# Microcontroller.net
KiCad netlist of a schematic drawn in Altium Designer
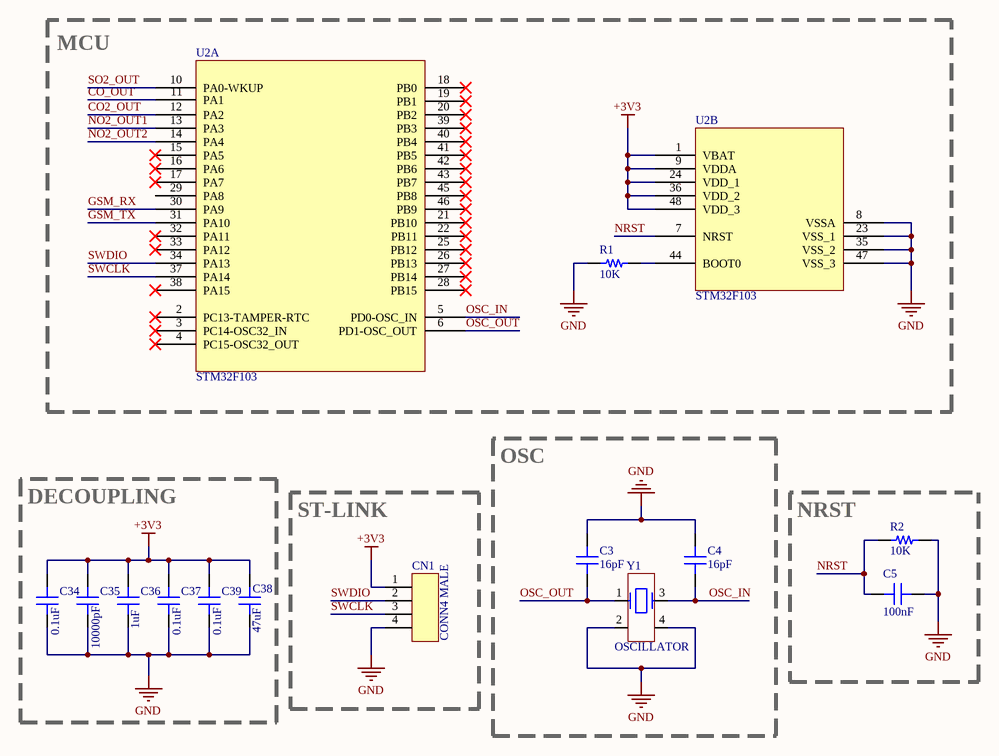
[diagram p0: Microcontroller.SchDoc]

(export (version "E")
  (design (tool "Eeschema 10.0.6"))
  (components
    (comp (ref "C3")
      (value "16pF")
      (footprint "CAP 0603_1608")
      (description "CERAMİC 1206 SMD")
      (libsource (lib "hava_kalitesi_olcumu") (part "16pF"))
    )
    (comp (ref "C4")
      (value "16pF")
      (footprint "CAP 0603_1608")
      (description "CERAMİC 1206 SMD")
      (libsource (lib "hava_kalitesi_olcumu") (part "16pF"))
    )
    (comp (ref "C5")
      (value "100nF")
      (footprint "CAP 0603_1608")
      (description "CERAMİC 1206 SMD")
      (libsource (lib "hava_kalitesi_olcumu") (part "100nF"))
    )
    (comp (ref "C34")
      (value "0.1uF")
      (footprint "CAP 0603_1608")
      (description "CERAMİC 1206 SMD")
      (libsource (lib "hava_kalitesi_olcumu") (part "0.1uF"))
    )
    (comp (ref "C35")
      (value "10000pF")
      (footprint "CAP 0603_1608")
      (description "CERAMİC 1206 SMD")
      (libsource (lib "hava_kalitesi_olcumu") (part "10000pF"))
    )
    (comp (ref "C36")
      (value "1uF")
      (footprint "CAP 0603_1608")
      (description "CERAMİC 1206 SMD")
      (libsource (lib "hava_kalitesi_olcumu") (part "1uF"))
    )
    (comp (ref "C37")
      (value "0.1uF")
      (footprint "CAP 0603_1608")
      (description "CERAMİC 1206 SMD")
      (libsource (lib "hava_kalitesi_olcumu") (part "0.1uF"))
    )
    (comp (ref "C38")
      (value "47uF")
      (footprint "CAP 0603_1608")
      (description "CERAMİC 1206 SMD")
      (libsource (lib "hava_kalitesi_olcumu") (part "47uF"))
    )
    (comp (ref "C39")
      (value "0.1uF")
      (footprint "CAP 0603_1608")
      (description "CERAMİC 1206 SMD")
      (libsource (lib "hava_kalitesi_olcumu") (part "0.1uF"))
    )
    (comp (ref "CN1")
      (value "CONN4 MALE")
      (footprint "CONN4 MALE")
      (description "4 PIN 2.54MM")
      (libsource (lib "hava_kalitesi_olcumu") (part "CONN4 MALE"))
    )
    (comp (ref "R1")
      (value "10K")
      (footprint "RES 0603_1608")
      (description "SMT RES 1206")
      (libsource (lib "hava_kalitesi_olcumu") (part "10K"))
    )
    (comp (ref "R2")
      (value "10K")
      (footprint "RES 0603_1608")
      (description "SMT RES 1206")
      (libsource (lib "hava_kalitesi_olcumu") (part "10K"))
    )
    (comp (ref "U2")
      (value "STM32F103")
      (footprint "LQFP48")
      (description "STM32F103C8T6 SMD LQFP-48 32-Bit 72 MHz Mikrodenetleyici")
      (libsource (lib "hava_kalitesi_olcumu") (part "STM32F103"))
    )
    (comp (ref "Y1")
      (value "OSCILLATOR")
      (footprint "OSCILLATOR")
      (description "8MHZ 12.5pF")
      (libsource (lib "hava_kalitesi_olcumu") (part "OSCILLATOR"))
    )
  )
  (nets
    (net (code "1") (name "+3V3") (class "Default")
      (node (ref "C34") (pin "2") (pinfunction "2_2") (pintype "passive"))
      (node (ref "C35") (pin "2") (pinfunction "2_2") (pintype "passive"))
      (node (ref "C36") (pin "2") (pinfunction "2_2") (pintype "passive"))
      (node (ref "C37") (pin "2") (pinfunction "2_2") (pintype "passive"))
      (node (ref "C38") (pin "2") (pinfunction "2_2") (pintype "passive"))
      (node (ref "C39") (pin "2") (pinfunction "2_2") (pintype "passive"))
      (node (ref "CN1") (pin "1") (pintype "passive"))
      (node (ref "U2") (pin "1") (pinfunction "VBAT_1") (pintype "passive"))
      (node (ref "U2") (pin "24") (pinfunction "VDD_1_24") (pintype "passive"))
      (node (ref "U2") (pin "36") (pinfunction "VDD_2_36") (pintype "passive"))
      (node (ref "U2") (pin "48") (pinfunction "VDD_3_48") (pintype "passive"))
      (node (ref "U2") (pin "9") (pinfunction "VDDA_9") (pintype "passive"))
    )
    (net (code "2") (name "/CO2_OUT") (class "Default")
      (node (ref "U2") (pin "12") (pinfunction "PA2_12") (pintype "passive"))
    )
    (net (code "3") (name "/CO_OUT") (class "Default")
      (node (ref "U2") (pin "11") (pinfunction "PA1_11") (pintype "passive"))
    )
    (net (code "4") (name "/GSM_RX") (class "Default")
      (node (ref "U2") (pin "30") (pinfunction "PA9_30") (pintype "passive"))
    )
    (net (code "5") (name "/GSM_TX") (class "Default")
      (node (ref "U2") (pin "31") (pinfunction "PA10_31") (pintype "passive"))
    )
    (net (code "6") (name "/NO2_OUT1") (class "Default")
      (node (ref "U2") (pin "13") (pinfunction "PA3_13") (pintype "passive"))
    )
    (net (code "7") (name "/NO2_OUT2") (class "Default")
      (node (ref "U2") (pin "14") (pinfunction "PA4_14") (pintype "passive"))
    )
    (net (code "8") (name "/NRST") (class "Default")
      (node (ref "C5") (pin "2") (pinfunction "2_2") (pintype "passive"))
      (node (ref "R2") (pin "1") (pinfunction "1_1") (pintype "passive"))
      (node (ref "U2") (pin "7") (pinfunction "NRST_7") (pintype "passive"))
    )
    (net (code "9") (name "/OSC_IN") (class "Default")
      (node (ref "C4") (pin "1") (pinfunction "1_1") (pintype "passive"))
      (node (ref "U2") (pin "5") (pinfunction "PD0-OSC_IN_5") (pintype "passive"))
      (node (ref "Y1") (pin "3") (pinfunction "3_3") (pintype "passive"))
    )
    (net (code "10") (name "/OSC_OUT") (class "Default")
      (node (ref "C3") (pin "1") (pinfunction "1_1") (pintype "passive"))
      (node (ref "U2") (pin "6") (pinfunction "PD1-OSC_OUT_6") (pintype "passive"))
      (node (ref "Y1") (pin "1") (pinfunction "1_1") (pintype "passive"))
    )
    (net (code "11") (name "/SO2_OUT") (class "Default")
      (node (ref "U2") (pin "10") (pinfunction "PA0-WKUP_10") (pintype "passive"))
    )
    (net (code "12") (name "/SWCLK") (class "Default")
      (node (ref "CN1") (pin "3") (pintype "passive"))
      (node (ref "U2") (pin "37") (pinfunction "PA14_37") (pintype "passive"))
    )
    (net (code "13") (name "/SWDIO") (class "Default")
      (node (ref "CN1") (pin "2") (pintype "passive"))
      (node (ref "U2") (pin "34") (pinfunction "PA13_34") (pintype "passive"))
    )
    (net (code "14") (name "GND") (class "Default")
      (node (ref "C3") (pin "2") (pinfunction "2_2") (pintype "passive"))
      (node (ref "C34") (pin "1") (pinfunction "1_1") (pintype "passive"))
      (node (ref "C35") (pin "1") (pinfunction "1_1") (pintype "passive"))
      (node (ref "C36") (pin "1") (pinfunction "1_1") (pintype "passive"))
      (node (ref "C37") (pin "1") (pinfunction "1_1") (pintype "passive"))
      (node (ref "C38") (pin "1") (pinfunction "1_1") (pintype "passive"))
      (node (ref "C39") (pin "1") (pinfunction "1_1") (pintype "passive"))
      (node (ref "C4") (pin "2") (pinfunction "2_2") (pintype "passive"))
      (node (ref "C5") (pin "1") (pinfunction "1_1") (pintype "passive"))
      (node (ref "CN1") (pin "4") (pintype "passive"))
      (node (ref "R1") (pin "1") (pinfunction "1_1") (pintype "passive"))
      (node (ref "R2") (pin "2") (pinfunction "2_2") (pintype "passive"))
      (node (ref "U2") (pin "23") (pinfunction "VSS_1_23") (pintype "passive"))
      (node (ref "U2") (pin "35") (pinfunction "VSS_2_35") (pintype "passive"))
      (node (ref "U2") (pin "47") (pinfunction "VSS_3_47") (pintype "passive"))
      (node (ref "U2") (pin "8") (pinfunction "VSSA_8") (pintype "passive"))
      (node (ref "Y1") (pin "2") (pinfunction "2_2") (pintype "passive"))
      (node (ref "Y1") (pin "4") (pinfunction "4_4") (pintype "passive"))
    )
    (net (code "15") (name "Net-(U2B-BOOT0)") (class "Default")
      (node (ref "R1") (pin "2") (pinfunction "2_2") (pintype "passive"))
      (node (ref "U2") (pin "44") (pinfunction "BOOT0_44") (pintype "passive"))
    )
    (net (code "16") (name "unconnected-(U2A-PA1-Pad11)") (class "Default")
      (node (ref "U2") (pin "11") (pinfunction "PA1_11") (pintype "passive"))
    )
    (net (code "17") (name "unconnected-(U2A-PA5-Pad15)") (class "Default")
      (node (ref "U2") (pin "15") (pinfunction "PA5_15") (pintype "passive+no_connect"))
    )
    (net (code "18") (name "unconnected-(U2A-PA6-Pad16)") (class "Default")
      (node (ref "U2") (pin "16") (pinfunction "PA6_16") (pintype "passive+no_connect"))
    )
    (net (code "19") (name "unconnected-(U2A-PA7-Pad17)") (class "Default")
      (node (ref "U2") (pin "17") (pinfunction "PA7_17") (pintype "passive+no_connect"))
    )
    (net (code "20") (name "unconnected-(U2A-PA8-Pad29)") (class "Default")
      (node (ref "U2") (pin "29") (pinfunction "PA8_29") (pintype "passive"))
    )
    (net (code "21") (name "unconnected-(U2A-PA11-Pad32)") (class "Default")
      (node (ref "U2") (pin "32") (pinfunction "PA11_32") (pintype "passive+no_connect"))
    )
    (net (code "22") (name "unconnected-(U2A-PA12-Pad33)") (class "Default")
      (node (ref "U2") (pin "33") (pinfunction "PA12_33") (pintype "passive+no_connect"))
    )
    (net (code "23") (name "unconnected-(U2A-PA15-Pad38)") (class "Default")
      (node (ref "U2") (pin "38") (pinfunction "PA15_38") (pintype "passive+no_connect"))
    )
    (net (code "24") (name "unconnected-(U2A-PB0-Pad18)") (class "Default")
      (node (ref "U2") (pin "18") (pinfunction "PB0_18") (pintype "passive+no_connect"))
    )
    (net (code "25") (name "unconnected-(U2A-PB1-Pad19)") (class "Default")
      (node (ref "U2") (pin "19") (pinfunction "PB1_19") (pintype "passive+no_connect"))
    )
    (net (code "26") (name "unconnected-(U2A-PB2-Pad20)") (class "Default")
      (node (ref "U2") (pin "20") (pinfunction "PB2_20") (pintype "passive+no_connect"))
    )
    (net (code "27") (name "unconnected-(U2A-PB3-Pad39)") (class "Default")
      (node (ref "U2") (pin "39") (pinfunction "PB3_39") (pintype "passive+no_connect"))
    )
    (net (code "28") (name "unconnected-(U2A-PB4-Pad40)") (class "Default")
      (node (ref "U2") (pin "40") (pinfunction "PB4_40") (pintype "passive+no_connect"))
    )
    (net (code "29") (name "unconnected-(U2A-PB5-Pad41)") (class "Default")
      (node (ref "U2") (pin "41") (pinfunction "PB5_41") (pintype "passive+no_connect"))
    )
    (net (code "30") (name "unconnected-(U2A-PB6-Pad42)") (class "Default")
      (node (ref "U2") (pin "42") (pinfunction "PB6_42") (pintype "passive+no_connect"))
    )
    (net (code "31") (name "unconnected-(U2A-PB7-Pad43)") (class "Default")
      (node (ref "U2") (pin "43") (pinfunction "PB7_43") (pintype "passive+no_connect"))
    )
    (net (code "32") (name "unconnected-(U2A-PB8-Pad45)") (class "Default")
      (node (ref "U2") (pin "45") (pinfunction "PB8_45") (pintype "passive+no_connect"))
    )
    (net (code "33") (name "unconnected-(U2A-PB9-Pad46)") (class "Default")
      (node (ref "U2") (pin "46") (pinfunction "PB9_46") (pintype "passive+no_connect"))
    )
    (net (code "34") (name "unconnected-(U2A-PB10-Pad21)") (class "Default")
      (node (ref "U2") (pin "21") (pinfunction "PB10_21") (pintype "passive+no_connect"))
    )
    (net (code "35") (name "unconnected-(U2A-PB11-Pad22)") (class "Default")
      (node (ref "U2") (pin "22") (pinfunction "PB11_22") (pintype "passive+no_connect"))
    )
    (net (code "36") (name "unconnected-(U2A-PB12-Pad25)") (class "Default")
      (node (ref "U2") (pin "25") (pinfunction "PB12_25") (pintype "passive+no_connect"))
    )
    (net (code "37") (name "unconnected-(U2A-PB13-Pad26)") (class "Default")
      (node (ref "U2") (pin "26") (pinfunction "PB13_26") (pintype "passive+no_connect"))
    )
    (net (code "38") (name "unconnected-(U2A-PB14-Pad27)") (class "Default")
      (node (ref "U2") (pin "27") (pinfunction "PB14_27") (pintype "passive+no_connect"))
    )
    (net (code "39") (name "unconnected-(U2A-PB15-Pad28)") (class "Default")
      (node (ref "U2") (pin "28") (pinfunction "PB15_28") (pintype "passive+no_connect"))
    )
    (net (code "40") (name "unconnected-(U2A-PC13-TAMPER-RTC-Pad2)") (class "Default")
      (node (ref "U2") (pin "2") (pinfunction "PC13-TAMPER-RTC_2") (pintype "passive+no_connect"))
    )
    (net (code "41") (name "unconnected-(U2A-PC14-OSC32_IN-Pad3)") (class "Default")
      (node (ref "U2") (pin "3") (pinfunction "PC14-OSC32_IN_3") (pintype "passive+no_connect"))
    )
    (net (code "42") (name "unconnected-(U2A-PC15-OSC32_OUT-Pad4)") (class "Default")
      (node (ref "U2") (pin "4") (pinfunction "PC15-OSC32_OUT_4") (pintype "passive+no_connect"))
    )
  )
)
